# mainboard-raspi-3.net
KiCad netlist of a schematic drawn in EAGLE
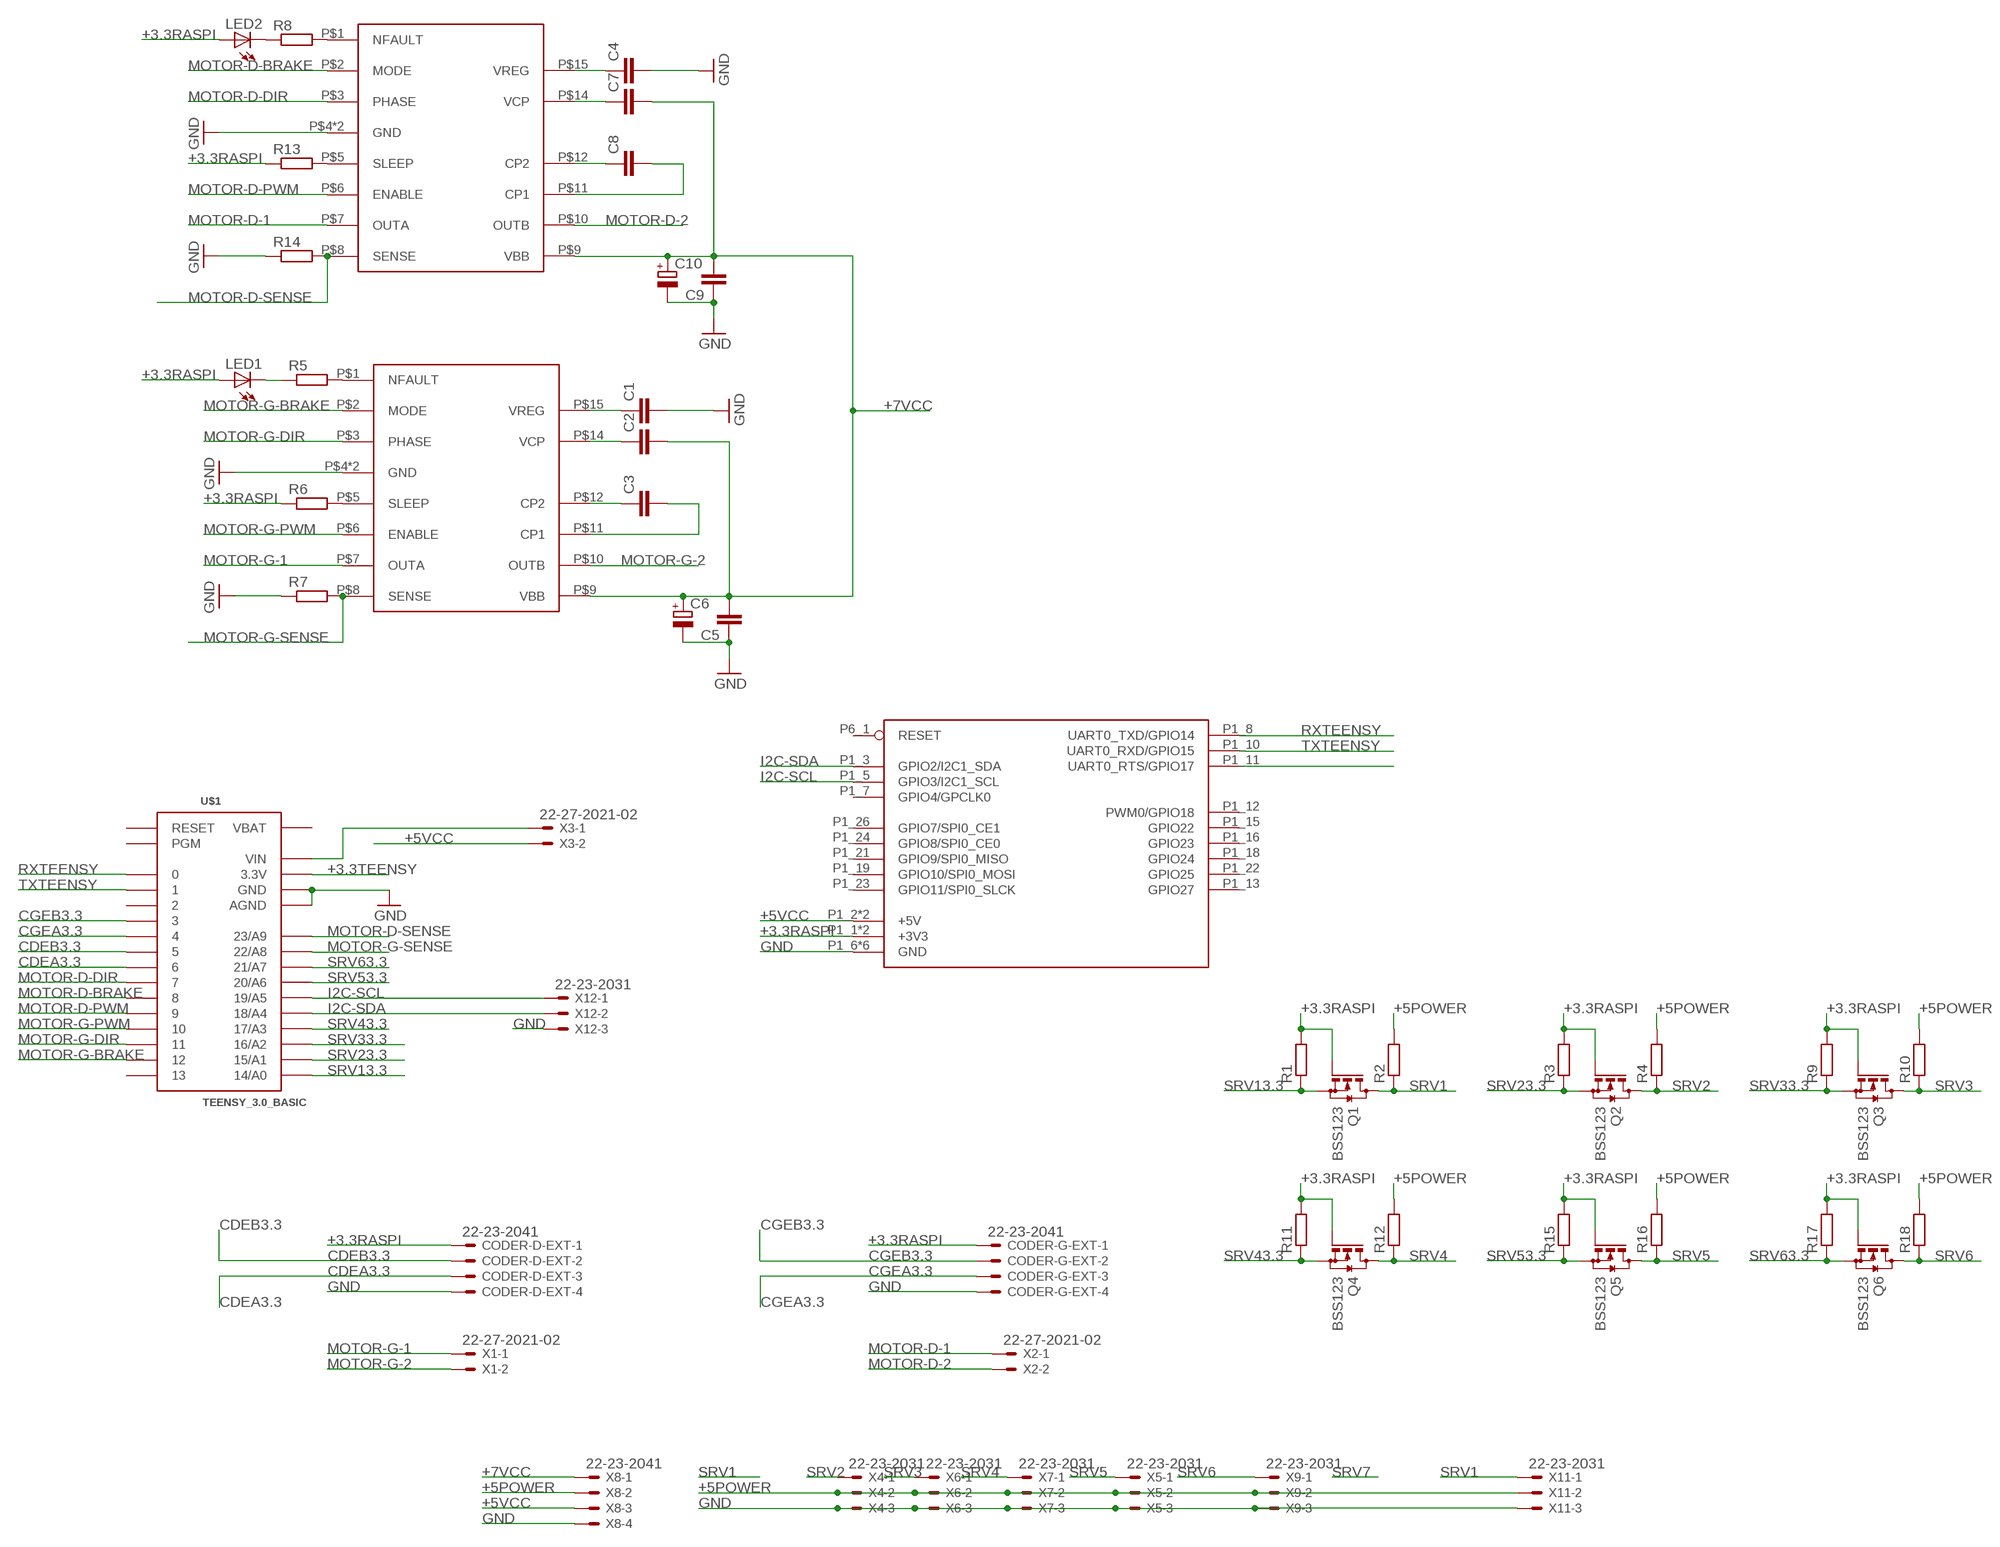
[diagram p0: schematic, sheet 1]

(export (version "E")
  (design (tool "Eeschema 10.0.6"))
  (components
    (comp (ref "C1")
      (value "C-EUC0805K")
      (footprint "eagle-import:C0805K")
      (libsource (lib "eagle-import") (part "C-EUC0805K"))
    )
    (comp (ref "C2")
      (value "C-EUC0805K")
      (footprint "eagle-import:C0805K")
      (libsource (lib "eagle-import") (part "C-EUC0805K"))
    )
    (comp (ref "C3")
      (value "C-EUC0805K")
      (footprint "eagle-import:C0805K")
      (libsource (lib "eagle-import") (part "C-EUC0805K"))
    )
    (comp (ref "C4")
      (value "C-EUC0805K")
      (footprint "eagle-import:C0805K")
      (libsource (lib "eagle-import") (part "C-EUC0805K"))
    )
    (comp (ref "C5")
      (value "C-EUC0805K")
      (footprint "eagle-import:C0805K")
      (libsource (lib "eagle-import") (part "C-EUC0805K"))
    )
    (comp (ref "C6")
      (value "CPOL-EUE3.5-8")
      (footprint "eagle-import:E3,5-8")
      (libsource (lib "eagle-import") (part "CPOL-EUE3.5-8"))
    )
    (comp (ref "C7")
      (value "C-EUC0805K")
      (footprint "eagle-import:C0805K")
      (libsource (lib "eagle-import") (part "C-EUC0805K"))
    )
    (comp (ref "C8")
      (value "C-EUC0805K")
      (footprint "eagle-import:C0805K")
      (libsource (lib "eagle-import") (part "C-EUC0805K"))
    )
    (comp (ref "C9")
      (value "C-EUC0805K")
      (footprint "eagle-import:C0805K")
      (libsource (lib "eagle-import") (part "C-EUC0805K"))
    )
    (comp (ref "C10")
      (value "CPOL-EUE3.5-8")
      (footprint "eagle-import:E3,5-8")
      (libsource (lib "eagle-import") (part "CPOL-EUE3.5-8"))
    )
    (comp (ref "CODER-D-EXT")
      (value "22-23-2041")
      (footprint "eagle-import:22-23-2041")
      (fields (field (name "MF") "MOLEX"))
      (libsource (lib "eagle-import") (part "22-23-2041"))
    )
    (comp (ref "CODER-G-EXT")
      (value "22-23-2041")
      (footprint "eagle-import:22-23-2041")
      (fields (field (name "MF") "MOLEX"))
      (libsource (lib "eagle-import") (part "22-23-2041"))
    )
    (comp (ref "LED1")
      (value "LED3MM")
      (footprint "eagle-import:LED3MM")
      (libsource (lib "eagle-import") (part "LED3MM"))
    )
    (comp (ref "LED2")
      (value "LED3MM")
      (footprint "eagle-import:LED3MM")
      (libsource (lib "eagle-import") (part "LED3MM"))
    )
    (comp (ref "Q1")
      (value "BSS123")
      (footprint "eagle-import:SOT23")
      (libsource (lib "eagle-import") (part "BSS123"))
    )
    (comp (ref "Q2")
      (value "BSS123")
      (footprint "eagle-import:SOT23")
      (libsource (lib "eagle-import") (part "BSS123"))
    )
    (comp (ref "Q3")
      (value "BSS123")
      (footprint "eagle-import:SOT23")
      (libsource (lib "eagle-import") (part "BSS123"))
    )
    (comp (ref "Q4")
      (value "BSS123")
      (footprint "eagle-import:SOT23")
      (libsource (lib "eagle-import") (part "BSS123"))
    )
    (comp (ref "Q5")
      (value "BSS123")
      (footprint "eagle-import:SOT23")
      (libsource (lib "eagle-import") (part "BSS123"))
    )
    (comp (ref "Q6")
      (value "BSS123")
      (footprint "eagle-import:SOT23")
      (libsource (lib "eagle-import") (part "BSS123"))
    )
    (comp (ref "R1")
      (value "R-EU_R0603")
      (footprint "eagle-import:R0603")
      (libsource (lib "eagle-import") (part "R-EU_R0603"))
    )
    (comp (ref "R2")
      (value "R-EU_R0603")
      (footprint "eagle-import:R0603")
      (libsource (lib "eagle-import") (part "R-EU_R0603"))
    )
    (comp (ref "R3")
      (value "R-EU_R0603")
      (footprint "eagle-import:R0603")
      (libsource (lib "eagle-import") (part "R-EU_R0603"))
    )
    (comp (ref "R4")
      (value "R-EU_R0603")
      (footprint "eagle-import:R0603")
      (libsource (lib "eagle-import") (part "R-EU_R0603"))
    )
    (comp (ref "R5")
      (value "R-EU_0204/7")
      (footprint "eagle-import:0204_7")
      (libsource (lib "eagle-import") (part "R-EU_0204/7"))
    )
    (comp (ref "R6")
      (value "R-EU_0204/5")
      (footprint "eagle-import:0204_5")
      (libsource (lib "eagle-import") (part "R-EU_0204/5"))
    )
    (comp (ref "R7")
      (value "R-EU_0204/5")
      (footprint "eagle-import:0204_5")
      (libsource (lib "eagle-import") (part "R-EU_0204/5"))
    )
    (comp (ref "R8")
      (value "R-EU_0204/7")
      (footprint "eagle-import:0204_7")
      (libsource (lib "eagle-import") (part "R-EU_0204/7"))
    )
    (comp (ref "R9")
      (value "R-EU_R0603")
      (footprint "eagle-import:R0603")
      (libsource (lib "eagle-import") (part "R-EU_R0603"))
    )
    (comp (ref "R10")
      (value "R-EU_R0603")
      (footprint "eagle-import:R0603")
      (libsource (lib "eagle-import") (part "R-EU_R0603"))
    )
    (comp (ref "R11")
      (value "R-EU_R0603")
      (footprint "eagle-import:R0603")
      (libsource (lib "eagle-import") (part "R-EU_R0603"))
    )
    (comp (ref "R12")
      (value "R-EU_R0603")
      (footprint "eagle-import:R0603")
      (libsource (lib "eagle-import") (part "R-EU_R0603"))
    )
    (comp (ref "R13")
      (value "R-EU_0204/5")
      (footprint "eagle-import:0204_5")
      (libsource (lib "eagle-import") (part "R-EU_0204/5"))
    )
    (comp (ref "R14")
      (value "R-EU_0204/5")
      (footprint "eagle-import:0204_5")
      (libsource (lib "eagle-import") (part "R-EU_0204/5"))
    )
    (comp (ref "R15")
      (value "R-EU_R0603")
      (footprint "eagle-import:R0603")
      (libsource (lib "eagle-import") (part "R-EU_R0603"))
    )
    (comp (ref "R16")
      (value "R-EU_R0603")
      (footprint "eagle-import:R0603")
      (libsource (lib "eagle-import") (part "R-EU_R0603"))
    )
    (comp (ref "R17")
      (value "R-EU_R0603")
      (footprint "eagle-import:R0603")
      (libsource (lib "eagle-import") (part "R-EU_R0603"))
    )
    (comp (ref "R18")
      (value "R-EU_R0603")
      (footprint "eagle-import:R0603")
      (libsource (lib "eagle-import") (part "R-EU_R0603"))
    )
    (comp (ref "U$1")
      (value "TEENSY_3.0_BASIC")
      (footprint "eagle-import:TEENSY_3.0_BASIC")
      (libsource (lib "eagle-import") (part "TEENSY_3.0_BASIC"))
    )
    (comp (ref "U$2")
      (value "RPI-B-V2SHIELD")
      (footprint "eagle-import:RPI-B-V2-SHIELD")
      (libsource (lib "eagle-import") (part "RPI-B-V2SHIELD"))
    )
    (comp (ref "U$3")
      (value "A3950-DIL")
      (footprint "eagle-import:DIL16")
      (libsource (lib "eagle-import") (part "A3950-DIL"))
    )
    (comp (ref "U$4")
      (value "A3950-DIL")
      (footprint "eagle-import:DIL16")
      (libsource (lib "eagle-import") (part "A3950-DIL"))
    )
    (comp (ref "X1")
      (value "22-27-2021-02")
      (footprint "eagle-import:6410-02")
      (libsource (lib "eagle-import") (part "22-?-0227-2021"))
    )
    (comp (ref "X2")
      (value "22-27-2021-02")
      (footprint "eagle-import:6410-02")
      (libsource (lib "eagle-import") (part "22-?-0227-2021"))
    )
    (comp (ref "X3")
      (value "22-27-2021-02")
      (footprint "eagle-import:6410-02")
      (libsource (lib "eagle-import") (part "22-?-0227-2021"))
    )
    (comp (ref "X4")
      (value "22-23-2031")
      (footprint "eagle-import:22-23-2031")
      (fields (field (name "MF") "MOLEX"))
      (libsource (lib "eagle-import") (part "22-23-2031"))
    )
    (comp (ref "X5")
      (value "22-23-2031")
      (footprint "eagle-import:22-23-2031")
      (fields (field (name "MF") "MOLEX"))
      (libsource (lib "eagle-import") (part "22-23-2031"))
    )
    (comp (ref "X6")
      (value "22-23-2031")
      (footprint "eagle-import:22-23-2031")
      (fields (field (name "MF") "MOLEX"))
      (libsource (lib "eagle-import") (part "22-23-2031"))
    )
    (comp (ref "X7")
      (value "22-23-2031")
      (footprint "eagle-import:22-23-2031")
      (fields (field (name "MF") "MOLEX"))
      (libsource (lib "eagle-import") (part "22-23-2031"))
    )
    (comp (ref "X8")
      (value "22-23-2041")
      (footprint "eagle-import:22-23-2041")
      (fields (field (name "MF") "MOLEX"))
      (libsource (lib "eagle-import") (part "22-23-2041"))
    )
    (comp (ref "X9")
      (value "22-23-2031")
      (footprint "eagle-import:22-23-2031")
      (fields (field (name "MF") "MOLEX"))
      (libsource (lib "eagle-import") (part "22-23-2031"))
    )
    (comp (ref "X11")
      (value "22-23-2031")
      (footprint "eagle-import:22-23-2031")
      (fields (field (name "MF") "MOLEX"))
      (libsource (lib "eagle-import") (part "22-23-2031"))
    )
    (comp (ref "X12")
      (value "22-23-2031")
      (footprint "eagle-import:22-23-2031")
      (fields (field (name "MF") "MOLEX"))
      (libsource (lib "eagle-import") (part "22-23-2031"))
    )
  )
  (nets
    (net (code "1") (name "/+3.3RASPI") (class "Default")
      (node (ref "CODER-D-EXT") (pin "1") (pinfunction "S_1") (pintype "passive"))
      (node (ref "CODER-G-EXT") (pin "1") (pinfunction "S_1") (pintype "passive"))
      (node (ref "LED1") (pin "A") (pinfunction "A_A") (pintype "passive"))
      (node (ref "LED2") (pin "A") (pinfunction "A_A") (pintype "passive"))
      (node (ref "Q1") (pin "1") (pinfunction "G_1") (pintype "passive"))
      (node (ref "Q2") (pin "1") (pinfunction "G_1") (pintype "passive"))
      (node (ref "Q3") (pin "1") (pinfunction "G_1") (pintype "passive"))
      (node (ref "Q4") (pin "1") (pinfunction "G_1") (pintype "passive"))
      (node (ref "Q5") (pin "1") (pinfunction "G_1") (pintype "passive"))
      (node (ref "Q6") (pin "1") (pinfunction "G_1") (pintype "passive"))
      (node (ref "R1") (pin "2") (pinfunction "2_2") (pintype "passive"))
      (node (ref "R11") (pin "2") (pinfunction "2_2") (pintype "passive"))
      (node (ref "R13") (pin "1") (pinfunction "1_1") (pintype "passive"))
      (node (ref "R15") (pin "2") (pinfunction "2_2") (pintype "passive"))
      (node (ref "R17") (pin "2") (pinfunction "2_2") (pintype "passive"))
      (node (ref "R3") (pin "2") (pinfunction "2_2") (pintype "passive"))
      (node (ref "R6") (pin "1") (pinfunction "1_1") (pintype "passive"))
      (node (ref "R9") (pin "2") (pinfunction "2_2") (pintype "passive"))
      (node (ref "U$2") (pin "P1_1") (pinfunction "+3V3_P1_1") (pintype "power_in"))
      (node (ref "U$2") (pin "P1_17") (pinfunction "+3V3_P1_17") (pintype "power_in"))
    )
    (net (code "2") (name "/+3.3TEENSY") (class "Default")
      (node (ref "U$1") (pin "3.3V") (pinfunction "3.3V_3.3V") (pintype "power_in"))
      (node (ref "U$1") (pin "3.3V1") (pinfunction "3.3V_3.3V1") (pintype "power_in"))
    )
    (net (code "3") (name "/+5POWER") (class "Default")
      (node (ref "R10") (pin "2") (pinfunction "2_2") (pintype "passive"))
      (node (ref "R12") (pin "2") (pinfunction "2_2") (pintype "passive"))
      (node (ref "R16") (pin "2") (pinfunction "2_2") (pintype "passive"))
      (node (ref "R18") (pin "2") (pinfunction "2_2") (pintype "passive"))
      (node (ref "R2") (pin "2") (pinfunction "2_2") (pintype "passive"))
      (node (ref "R4") (pin "2") (pinfunction "2_2") (pintype "passive"))
      (node (ref "X11") (pin "2") (pinfunction "S_2") (pintype "passive"))
      (node (ref "X4") (pin "2") (pinfunction "S_2") (pintype "passive"))
      (node (ref "X5") (pin "2") (pinfunction "S_2") (pintype "passive"))
      (node (ref "X6") (pin "2") (pinfunction "S_2") (pintype "passive"))
      (node (ref "X7") (pin "2") (pinfunction "S_2") (pintype "passive"))
      (node (ref "X8") (pin "2") (pinfunction "S_2") (pintype "passive"))
      (node (ref "X9") (pin "2") (pinfunction "S_2") (pintype "passive"))
    )
    (net (code "4") (name "/+5VCC") (class "Default")
      (node (ref "U$2") (pin "P1_2") (pinfunction "+5V_P1_2") (pintype "power_in"))
      (node (ref "U$2") (pin "P1_4") (pinfunction "+5V_P1_4") (pintype "power_in"))
      (node (ref "X3") (pin "2") (pinfunction "S_2") (pintype "passive"))
      (node (ref "X8") (pin "3") (pinfunction "S_3") (pintype "passive"))
    )
    (net (code "5") (name "/+7VCC") (class "Default")
      (node (ref "C10") (pin "+") (pinfunction "+_+") (pintype "passive"))
      (node (ref "C2") (pin "2") (pinfunction "2_2") (pintype "passive"))
      (node (ref "C5") (pin "2") (pinfunction "2_2") (pintype "passive"))
      (node (ref "C6") (pin "+") (pinfunction "+_+") (pintype "passive"))
      (node (ref "C7") (pin "2") (pinfunction "2_2") (pintype "passive"))
      (node (ref "C9") (pin "2") (pinfunction "2_2") (pintype "passive"))
      (node (ref "U$3") (pin "P$9") (pinfunction "VBB_P$9") (pintype "bidirectional"))
      (node (ref "U$4") (pin "P$9") (pinfunction "VBB_P$9") (pintype "bidirectional"))
      (node (ref "X8") (pin "1") (pinfunction "S_1") (pintype "passive"))
    )
    (net (code "6") (name "/CDEA3.3") (class "Default")
      (node (ref "CODER-D-EXT") (pin "3") (pinfunction "S_3") (pintype "passive"))
      (node (ref "U$1") (pin "6") (pinfunction "6_6") (pintype "bidirectional"))
    )
    (net (code "7") (name "/CDEB3.3") (class "Default")
      (node (ref "CODER-D-EXT") (pin "2") (pinfunction "S_2") (pintype "passive"))
      (node (ref "U$1") (pin "5") (pinfunction "5_5") (pintype "bidirectional"))
    )
    (net (code "8") (name "/CGEA3.3") (class "Default")
      (node (ref "CODER-G-EXT") (pin "3") (pinfunction "S_3") (pintype "passive"))
      (node (ref "U$1") (pin "4") (pinfunction "4_4") (pintype "bidirectional"))
    )
    (net (code "9") (name "/CGEB3.3") (class "Default")
      (node (ref "CODER-G-EXT") (pin "2") (pinfunction "S_2") (pintype "passive"))
      (node (ref "U$1") (pin "3") (pinfunction "3_3") (pintype "bidirectional"))
    )
    (net (code "10") (name "/I2C-SCL") (class "Default")
      (node (ref "U$1") (pin "19/A5") (pinfunction "19/A5_19/A5") (pintype "bidirectional"))
      (node (ref "U$2") (pin "P1_5") (pinfunction "GPIO3/I2C1_SCL_P1_5") (pintype "bidirectional"))
      (node (ref "X12") (pin "1") (pinfunction "S_1") (pintype "passive"))
    )
    (net (code "11") (name "/I2C-SDA") (class "Default")
      (node (ref "U$1") (pin "18/A4") (pinfunction "18/A4_18/A4") (pintype "bidirectional"))
      (node (ref "U$2") (pin "P1_3") (pinfunction "GPIO2/I2C1_SDA_P1_3") (pintype "bidirectional"))
      (node (ref "X12") (pin "2") (pinfunction "S_2") (pintype "passive"))
    )
    (net (code "12") (name "/MOTOR-D-1") (class "Default")
      (node (ref "U$4") (pin "P$7") (pinfunction "OUTA_P$7") (pintype "bidirectional"))
      (node (ref "X2") (pin "1") (pinfunction "S_1") (pintype "passive"))
    )
    (net (code "13") (name "/MOTOR-D-2") (class "Default")
      (node (ref "U$4") (pin "P$10") (pinfunction "OUTB_P$10") (pintype "bidirectional"))
      (node (ref "X2") (pin "2") (pinfunction "S_2") (pintype "passive"))
    )
    (net (code "14") (name "/MOTOR-D-BRAKE") (class "Default")
      (node (ref "U$1") (pin "8") (pinfunction "8_8") (pintype "bidirectional"))
      (node (ref "U$4") (pin "P$2") (pinfunction "MODE_P$2") (pintype "bidirectional"))
    )
    (net (code "15") (name "/MOTOR-D-DIR") (class "Default")
      (node (ref "U$1") (pin "7") (pinfunction "7_7") (pintype "bidirectional"))
      (node (ref "U$4") (pin "P$3") (pinfunction "PHASE_P$3") (pintype "bidirectional"))
    )
    (net (code "16") (name "/MOTOR-D-PWM") (class "Default")
      (node (ref "U$1") (pin "9") (pinfunction "9_9") (pintype "bidirectional"))
      (node (ref "U$4") (pin "P$6") (pinfunction "ENABLE_P$6") (pintype "bidirectional"))
    )
    (net (code "17") (name "/MOTOR-D-SENSE") (class "Default")
      (node (ref "R14") (pin "2") (pinfunction "2_2") (pintype "passive"))
      (node (ref "U$1") (pin "23/A9") (pinfunction "23/A9_23/A9") (pintype "bidirectional"))
      (node (ref "U$4") (pin "P$8") (pinfunction "SENSE_P$8") (pintype "bidirectional"))
    )
    (net (code "18") (name "/MOTOR-G-1") (class "Default")
      (node (ref "U$3") (pin "P$7") (pinfunction "OUTA_P$7") (pintype "bidirectional"))
      (node (ref "X1") (pin "1") (pinfunction "S_1") (pintype "passive"))
    )
    (net (code "19") (name "/MOTOR-G-2") (class "Default")
      (node (ref "U$3") (pin "P$10") (pinfunction "OUTB_P$10") (pintype "bidirectional"))
      (node (ref "X1") (pin "2") (pinfunction "S_2") (pintype "passive"))
    )
    (net (code "20") (name "/MOTOR-G-BRAKE") (class "Default")
      (node (ref "U$1") (pin "12") (pinfunction "12_12") (pintype "bidirectional"))
      (node (ref "U$3") (pin "P$2") (pinfunction "MODE_P$2") (pintype "bidirectional"))
    )
    (net (code "21") (name "/MOTOR-G-DIR") (class "Default")
      (node (ref "U$1") (pin "11") (pinfunction "11_11") (pintype "bidirectional"))
      (node (ref "U$3") (pin "P$3") (pinfunction "PHASE_P$3") (pintype "bidirectional"))
    )
    (net (code "22") (name "/MOTOR-G-PWM") (class "Default")
      (node (ref "U$1") (pin "10") (pinfunction "10_10") (pintype "bidirectional"))
      (node (ref "U$3") (pin "P$6") (pinfunction "ENABLE_P$6") (pintype "bidirectional"))
    )
    (net (code "23") (name "/MOTOR-G-SENSE") (class "Default")
      (node (ref "R7") (pin "2") (pinfunction "2_2") (pintype "passive"))
      (node (ref "U$1") (pin "22/A8") (pinfunction "22/A8_22/A8") (pintype "bidirectional"))
      (node (ref "U$3") (pin "P$8") (pinfunction "SENSE_P$8") (pintype "bidirectional"))
    )
    (net (code "24") (name "/RESET") (class "Default")
      (node (ref "U$2") (pin "P6_1") (pinfunction "RESET_P6_1") (pintype "power_in"))
    )
    (net (code "25") (name "/RXTEENSY") (class "Default")
      (node (ref "U$1") (pin "0") (pinfunction "0_0") (pintype "bidirectional"))
      (node (ref "U$2") (pin "P1_8") (pinfunction "UART0_TXD/GPIO14_P1_8") (pintype "bidirectional"))
    )
    (net (code "26") (name "/SRV1") (class "Default")
      (node (ref "Q1") (pin "3") (pinfunction "D_3") (pintype "passive"))
      (node (ref "R2") (pin "1") (pinfunction "1_1") (pintype "passive"))
      (node (ref "X11") (pin "1") (pinfunction "S_1") (pintype "passive"))
    )
    (net (code "27") (name "/SRV2") (class "Default")
      (node (ref "Q2") (pin "3") (pinfunction "D_3") (pintype "passive"))
      (node (ref "R4") (pin "1") (pinfunction "1_1") (pintype "passive"))
      (node (ref "X4") (pin "1") (pinfunction "S_1") (pintype "passive"))
    )
    (net (code "28") (name "/SRV3") (class "Default")
      (node (ref "Q3") (pin "3") (pinfunction "D_3") (pintype "passive"))
      (node (ref "R10") (pin "1") (pinfunction "1_1") (pintype "passive"))
      (node (ref "X6") (pin "1") (pinfunction "S_1") (pintype "passive"))
    )
    (net (code "29") (name "/SRV4") (class "Default")
      (node (ref "Q4") (pin "3") (pinfunction "D_3") (pintype "passive"))
      (node (ref "R12") (pin "1") (pinfunction "1_1") (pintype "passive"))
      (node (ref "X7") (pin "1") (pinfunction "S_1") (pintype "passive"))
    )
    (net (code "30") (name "/SRV5") (class "Default")
      (node (ref "Q5") (pin "3") (pinfunction "D_3") (pintype "passive"))
      (node (ref "R16") (pin "1") (pinfunction "1_1") (pintype "passive"))
      (node (ref "X5") (pin "1") (pinfunction "S_1") (pintype "passive"))
    )
    (net (code "31") (name "/SRV6") (class "Default")
      (node (ref "Q6") (pin "3") (pinfunction "D_3") (pintype "passive"))
      (node (ref "R18") (pin "1") (pinfunction "1_1") (pintype "passive"))
      (node (ref "X9") (pin "1") (pinfunction "S_1") (pintype "passive"))
    )
    (net (code "33") (name "/SRV13.3") (class "Default")
      (node (ref "Q1") (pin "2") (pinfunction "S_2") (pintype "passive"))
      (node (ref "R1") (pin "1") (pinfunction "1_1") (pintype "passive"))
      (node (ref "U$1") (pin "14/A0") (pinfunction "14/A0_14/A0") (pintype "bidirectional"))
    )
    (net (code "34") (name "/SRV23.3") (class "Default")
      (node (ref "Q2") (pin "2") (pinfunction "S_2") (pintype "passive"))
      (node (ref "R3") (pin "1") (pinfunction "1_1") (pintype "passive"))
      (node (ref "U$1") (pin "15/A1") (pinfunction "15/A1_15/A1") (pintype "bidirectional"))
    )
    (net (code "35") (name "/SRV33.3") (class "Default")
      (node (ref "Q3") (pin "2") (pinfunction "S_2") (pintype "passive"))
      (node (ref "R9") (pin "1") (pinfunction "1_1") (pintype "passive"))
      (node (ref "U$1") (pin "16/A2") (pinfunction "16/A2_16/A2") (pintype "bidirectional"))
    )
    (net (code "36") (name "/SRV43.3") (class "Default")
      (node (ref "Q4") (pin "2") (pinfunction "S_2") (pintype "passive"))
      (node (ref "R11") (pin "1") (pinfunction "1_1") (pintype "passive"))
      (node (ref "U$1") (pin "17/A3") (pinfunction "17/A3_17/A3") (pintype "bidirectional"))
    )
    (net (code "37") (name "/SRV53.3") (class "Default")
      (node (ref "Q5") (pin "2") (pinfunction "S_2") (pintype "passive"))
      (node (ref "R15") (pin "1") (pinfunction "1_1") (pintype "passive"))
      (node (ref "U$1") (pin "20/A6") (pinfunction "20/A6_20/A6") (pintype "bidirectional"))
    )
    (net (code "38") (name "/SRV63.3") (class "Default")
      (node (ref "Q6") (pin "2") (pinfunction "S_2") (pintype "passive"))
      (node (ref "R17") (pin "1") (pinfunction "1_1") (pintype "passive"))
      (node (ref "U$1") (pin "21/A7") (pinfunction "21/A7_21/A7") (pintype "bidirectional"))
    )
    (net (code "39") (name "/TXTEENSY") (class "Default")
      (node (ref "U$1") (pin "1") (pinfunction "1_1") (pintype "bidirectional"))
      (node (ref "U$2") (pin "P1_10") (pinfunction "UART0_RXD/GPIO15_P1_10") (pintype "bidirectional"))
    )
    (net (code "40") (name "/VBAT") (class "Default")
      (node (ref "U$1") (pin "VBAT") (pinfunction "VBAT_VBAT") (pintype "power_in"))
    )
    (net (code "41") (name "GND") (class "Default")
      (node (ref "C1") (pin "2") (pinfunction "2_2") (pintype "passive"))
      (node (ref "C10") (pin "-") (pinfunction "-_-") (pintype "passive"))
      (node (ref "C4") (pin "2") (pinfunction "2_2") (pintype "passive"))
      (node (ref "C5") (pin "1") (pinfunction "1_1") (pintype "passive"))
      (node (ref "C6") (pin "-") (pinfunction "-_-") (pintype "passive"))
      (node (ref "C9") (pin "1") (pinfunction "1_1") (pintype "passive"))
      (node (ref "CODER-D-EXT") (pin "4") (pinfunction "S_4") (pintype "passive"))
      (node (ref "CODER-G-EXT") (pin "4") (pinfunction "S_4") (pintype "passive"))
      (node (ref "R14") (pin "1") (pinfunction "1_1") (pintype "passive"))
      (node (ref "R7") (pin "1") (pinfunction "1_1") (pintype "passive"))
      (node (ref "U$1") (pin "AGND") (pinfunction "AGND_AGND") (pintype "power_in"))
      (node (ref "U$1") (pin "GND") (pinfunction "GND_GND") (pintype "power_in"))
      (node (ref "U$1") (pin "GND1") (pinfunction "GND_GND1") (pintype "power_in"))
      (node (ref "U$2") (pin "P1_14") (pinfunction "GND_P1_14") (pintype "power_in"))
      (node (ref "U$2") (pin "P1_20") (pinfunction "GND_P1_20") (pintype "power_in"))
      (node (ref "U$2") (pin "P1_25") (pinfunction "GND_P1_25") (pintype "power_in"))
      (node (ref "U$2") (pin "P1_6") (pinfunction "GND_P1_6") (pintype "power_in"))
      (node (ref "U$2") (pin "P1_9") (pinfunction "GND_P1_9") (pintype "power_in"))
      (node (ref "U$2") (pin "P6_2") (pinfunction "GND_P6_2") (pintype "power_in"))
      (node (ref "U$3") (pin "P$13") (pinfunction "GND_P$13") (pintype "bidirectional"))
      (node (ref "U$3") (pin "P$4") (pinfunction "GND_P$4") (pintype "bidirectional"))
      (node (ref "U$4") (pin "P$13") (pinfunction "GND_P$13") (pintype "bidirectional"))
      (node (ref "U$4") (pin "P$4") (pinfunction "GND_P$4") (pintype "bidirectional"))
      (node (ref "X11") (pin "3") (pinfunction "S_3") (pintype "passive"))
      (node (ref "X12") (pin "3") (pinfunction "S_3") (pintype "passive"))
      (node (ref "X4") (pin "3") (pinfunction "S_3") (pintype "passive"))
      (node (ref "X5") (pin "3") (pinfunction "S_3") (pintype "passive"))
      (node (ref "X6") (pin "3") (pinfunction "S_3") (pintype "passive"))
      (node (ref "X7") (pin "3") (pinfunction "S_3") (pintype "passive"))
      (node (ref "X8") (pin "4") (pinfunction "S_4") (pintype "passive"))
      (node (ref "X9") (pin "3") (pinfunction "S_3") (pintype "passive"))
    )
    (net (code "42") (name "Net-(LED1-C)") (class "Default")
      (node (ref "LED1") (pin "K") (pinfunction "C_K") (pintype "passive"))
      (node (ref "R5") (pin "1") (pinfunction "1_1") (pintype "passive"))
    )
    (net (code "43") (name "Net-(LED2-C)") (class "Default")
      (node (ref "LED2") (pin "K") (pinfunction "C_K") (pintype "passive"))
      (node (ref "R8") (pin "1") (pinfunction "1_1") (pintype "passive"))
    )
    (net (code "44") (name "Net-(U$3-CP1)") (class "Default")
      (node (ref "C3") (pin "2") (pinfunction "2_2") (pintype "passive"))
      (node (ref "U$3") (pin "P$11") (pinfunction "CP1_P$11") (pintype "bidirectional"))
    )
    (net (code "45") (name "Net-(U$3-CP2)") (class "Default")
      (node (ref "C3") (pin "1") (pinfunction "1_1") (pintype "passive"))
      (node (ref "U$3") (pin "P$12") (pinfunction "CP2_P$12") (pintype "bidirectional"))
    )
    (net (code "46") (name "Net-(U$3-NFAULT)") (class "Default")
      (node (ref "R5") (pin "2") (pinfunction "2_2") (pintype "passive"))
      (node (ref "U$3") (pin "P$1") (pinfunction "NFAULT_P$1") (pintype "bidirectional"))
    )
    (net (code "47") (name "Net-(U$3-SLEEP)") (class "Default")
      (node (ref "R6") (pin "2") (pinfunction "2_2") (pintype "passive"))
      (node (ref "U$3") (pin "P$5") (pinfunction "SLEEP_P$5") (pintype "bidirectional"))
    )
    (net (code "48") (name "Net-(U$3-VCP)") (class "Default")
      (node (ref "C2") (pin "1") (pinfunction "1_1") (pintype "passive"))
      (node (ref "U$3") (pin "P$14") (pinfunction "VCP_P$14") (pintype "bidirectional"))
    )
    (net (code "49") (name "Net-(U$3-VREG)") (class "Default")
      (node (ref "C1") (pin "1") (pinfunction "1_1") (pintype "passive"))
      (node (ref "U$3") (pin "P$15") (pinfunction "VREG_P$15") (pintype "bidirectional"))
    )
    (net (code "50") (name "Net-(U$4-CP1)") (class "Default")
      (node (ref "C8") (pin "2") (pinfunction "2_2") (pintype "passive"))
      (node (ref "U$4") (pin "P$11") (pinfunction "CP1_P$11") (pintype "bidirectional"))
    )
    (net (code "51") (name "Net-(U$4-CP2)") (class "Default")
      (node (ref "C8") (pin "1") (pinfunction "1_1") (pintype "passive"))
      (node (ref "U$4") (pin "P$12") (pinfunction "CP2_P$12") (pintype "bidirectional"))
    )
    (net (code "52") (name "Net-(U$4-NFAULT)") (class "Default")
      (node (ref "R8") (pin "2") (pinfunction "2_2") (pintype "passive"))
      (node (ref "U$4") (pin "P$1") (pinfunction "NFAULT_P$1") (pintype "bidirectional"))
    )
    (net (code "53") (name "Net-(U$4-SLEEP)") (class "Default")
      (node (ref "R13") (pin "2") (pinfunction "2_2") (pintype "passive"))
      (node (ref "U$4") (pin "P$5") (pinfunction "SLEEP_P$5") (pintype "bidirectional"))
    )
    (net (code "54") (name "Net-(U$4-VCP)") (class "Default")
      (node (ref "C7") (pin "1") (pinfunction "1_1") (pintype "passive"))
      (node (ref "U$4") (pin "P$14") (pinfunction "VCP_P$14") (pintype "bidirectional"))
    )
    (net (code "55") (name "Net-(U$4-VREG)") (class "Default")
      (node (ref "C4") (pin "1") (pinfunction "1_1") (pintype "passive"))
      (node (ref "U$4") (pin "P$15") (pinfunction "VREG_P$15") (pintype "bidirectional"))
    )
    (net (code "56") (name "Net-(X3A-S)") (class "Default")
      (node (ref "U$1") (pin "VIN") (pinfunction "VIN_VIN") (pintype "power_in"))
      (node (ref "X3") (pin "1") (pinfunction "S_1") (pintype "passive"))
    )
    (net (code "57") (name "unconnected-(U$1-Pad2)") (class "Default")
      (node (ref "U$1") (pin "2") (pinfunction "2_2") (pintype "bidirectional"))
    )
    (net (code "58") (name "unconnected-(U$1-Pad13)") (class "Default")
      (node (ref "U$1") (pin "13") (pinfunction "13_13") (pintype "bidirectional"))
    )
    (net (code "59") (name "unconnected-(U$1-PadPGM)") (class "Default")
      (node (ref "U$1") (pin "PGM") (pinfunction "PGM_PGM") (pintype "bidirectional"))
    )
    (net (code "60") (name "unconnected-(U$1-PadRESET)") (class "Default")
      (node (ref "U$1") (pin "RESET") (pinfunction "RESET_RESET") (pintype "bidirectional"))
    )
    (net (code "61") (name "unconnected-(U$2-GPIO4{slash}GPCLK0-PadP1_7)") (class "Default")
      (node (ref "U$2") (pin "P1_7") (pinfunction "GPIO4/GPCLK0_P1_7") (pintype "bidirectional"))
    )
    (net (code "62") (name "unconnected-(U$2-GPIO7{slash}SPI0_CE1-PadP1_26)") (class "Default")
      (node (ref "U$2") (pin "P1_26") (pinfunction "GPIO7/SPI0_CE1_P1_26") (pintype "bidirectional"))
    )
    (net (code "63") (name "unconnected-(U$2-GPIO8{slash}SPI0_CE0-PadP1_24)") (class "Default")
      (node (ref "U$2") (pin "P1_24") (pinfunction "GPIO8/SPI0_CE0_P1_24") (pintype "bidirectional"))
    )
    (net (code "64") (name "unconnected-(U$2-GPIO9{slash}SPI0_MISO-PadP1_21)") (class "Default")
      (node (ref "U$2") (pin "P1_21") (pinfunction "GPIO9/SPI0_MISO_P1_21") (pintype "bidirectional"))
    )
    (net (code "65") (name "unconnected-(U$2-GPIO10{slash}SPI0_MOSI-PadP1_19)") (class "Default")
      (node (ref "U$2") (pin "P1_19") (pinfunction "GPIO10/SPI0_MOSI_P1_19") (pintype "bidirectional"))
    )
    (net (code "66") (name "unconnected-(U$2-GPIO11{slash}SPI0_SLCK-PadP1_23)") (class "Default")
      (node (ref "U$2") (pin "P1_23") (pinfunction "GPIO11/SPI0_SLCK_P1_23") (pintype "bidirectional"))
    )
    (net (code "67") (name "unconnected-(U$2-GPIO22-PadP1_15)") (class "Default")
      (node (ref "U$2") (pin "P1_15") (pinfunction "GPIO22_P1_15") (pintype "bidirectional"))
    )
    (net (code "68") (name "unconnected-(U$2-GPIO23-PadP1_16)") (class "Default")
      (node (ref "U$2") (pin "P1_16") (pinfunction "GPIO23_P1_16") (pintype "bidirectional"))
    )
    (net (code "69") (name "unconnected-(U$2-GPIO24-PadP1_18)") (class "Default")
      (node (ref "U$2") (pin "P1_18") (pinfunction "GPIO24_P1_18") (pintype "bidirectional"))
    )
    (net (code "70") (name "unconnected-(U$2-GPIO25-PadP1_22)") (class "Default")
      (node (ref "U$2") (pin "P1_22") (pinfunction "GPIO25_P1_22") (pintype "bidirectional"))
    )
    (net (code "71") (name "unconnected-(U$2-GPIO27-PadP1_13)") (class "Default")
      (node (ref "U$2") (pin "P1_13") (pinfunction "GPIO27_P1_13") (pintype "bidirectional"))
    )
    (net (code "72") (name "unconnected-(U$2-PWM0{slash}GPIO18-PadP1_12)") (class "Default")
      (node (ref "U$2") (pin "P1_12") (pinfunction "PWM0/GPIO18_P1_12") (pintype "bidirectional"))
    )
    (net (code "73") (name "unconnected-(U$2-UART0_RTS{slash}GPIO17-PadP1_11)") (class "Default")
      (node (ref "U$2") (pin "P1_11") (pinfunction "UART0_RTS/GPIO17_P1_11") (pintype "bidirectional"))
    )
  )
)
